# reference_0v5_ADR130.net
KiCad netlist of a schematic drawn in Altium Designer
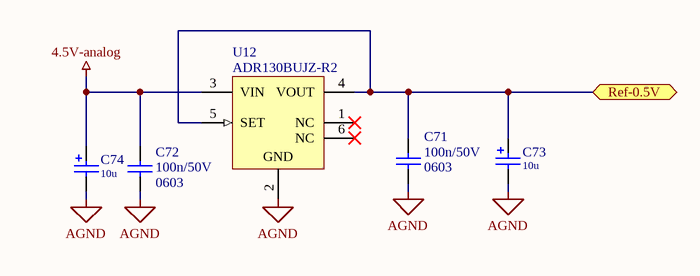
[diagram p0: reference_0v5_ADR130.SchDoc]

(export (version "E")
  (design (tool "Eeschema 10.0.6"))
  (components
    (comp (ref "C71")
      (value "100n/50V")
      (footprint "SMD_Capacitor_0603")
      (description "Ceramic Cap Kemet COTS 100n/50V X7R 0603")
      (fields
        (field (name "MANUFACTURER") "Kemet")
        (field (name "MANUFACTURERPARTNUMBER") "C0603T104K5RALTU")
        (field (name "PACKAGE") "0603")
      )
      (libsource (lib "capacitors") (part "Cer_C0603T104K5RALTU"))
    )
    (comp (ref "C72")
      (value "100n/50V")
      (footprint "SMD_Capacitor_0603")
      (description "Ceramic Cap Kemet COTS 100n/50V X7R 0603")
      (fields
        (field (name "MANUFACTURER") "Kemet")
        (field (name "MANUFACTURERPARTNUMBER") "C0603T104K5RALTU")
        (field (name "PACKAGE") "0603")
      )
      (libsource (lib "capacitors") (part "Cer_C0603T104K5RALTU"))
    )
    (comp (ref "C73")
      (value "10u")
      (footprint "Tantalum_cap_B")
      (description "Tantalum Capacitor")
      (libsource (lib "GG") (part "Cap Tantalum"))
    )
    (comp (ref "C74")
      (value "10u")
      (footprint "Tantalum_cap_B")
      (description "Tantalum Capacitor")
      (libsource (lib "GG") (part "Cap Tantalum"))
    )
    (comp (ref "U12")
      (value "ADR130BUJZ-R2")
      (footprint "ADI-UJ-6_M")
      (fields (field (name "MANUFACTURER") "Analog Devices"))
      (libsource (lib "Analog Devices Amplifiers and Linear Voltage References") (part "ADR130BUJZ-R2"))
    )
  )
  (nets
    (net (code "1") (name "/Ref-0.5V") (class "Default")
      (node (ref "C71") (pin "1") (pinfunction "1_1") (pintype "passive"))
      (node (ref "C73") (pin "1") (pinfunction "1_1") (pintype "passive"))
      (node (ref "U12") (pin "4") (pinfunction "VOUT_4") (pintype "power_in"))
      (node (ref "U12") (pin "5") (pinfunction "SET_5") (pintype "input"))
    )
    (net (code "2") (name "4.5V-analog") (class "Default")
      (node (ref "C72") (pin "1") (pinfunction "1_1") (pintype "passive"))
      (node (ref "C74") (pin "1") (pinfunction "1_1") (pintype "passive"))
      (node (ref "U12") (pin "3") (pinfunction "VIN_3") (pintype "power_in"))
    )
    (net (code "3") (name "AGND") (class "Default")
      (node (ref "C71") (pin "2") (pinfunction "2_2") (pintype "passive"))
      (node (ref "C72") (pin "2") (pinfunction "2_2") (pintype "passive"))
      (node (ref "C73") (pin "2") (pinfunction "2_2") (pintype "passive"))
      (node (ref "C74") (pin "2") (pinfunction "2_2") (pintype "passive"))
      (node (ref "U12") (pin "2") (pinfunction "GND_2") (pintype "power_in"))
    )
    (net (code "4") (name "unconnected-(U12-NC-Pad1)") (class "Default")
      (node (ref "U12") (pin "1") (pinfunction "NC_1") (pintype "passive+no_connect"))
    )
    (net (code "5") (name "unconnected-(U12-NC-Pad6)") (class "Default")
      (node (ref "U12") (pin "6") (pinfunction "NC_6") (pintype "passive+no_connect"))
    )
  )
)
